# CLK_SYNTH.net
KiCad netlist of a schematic drawn in Altium Designer
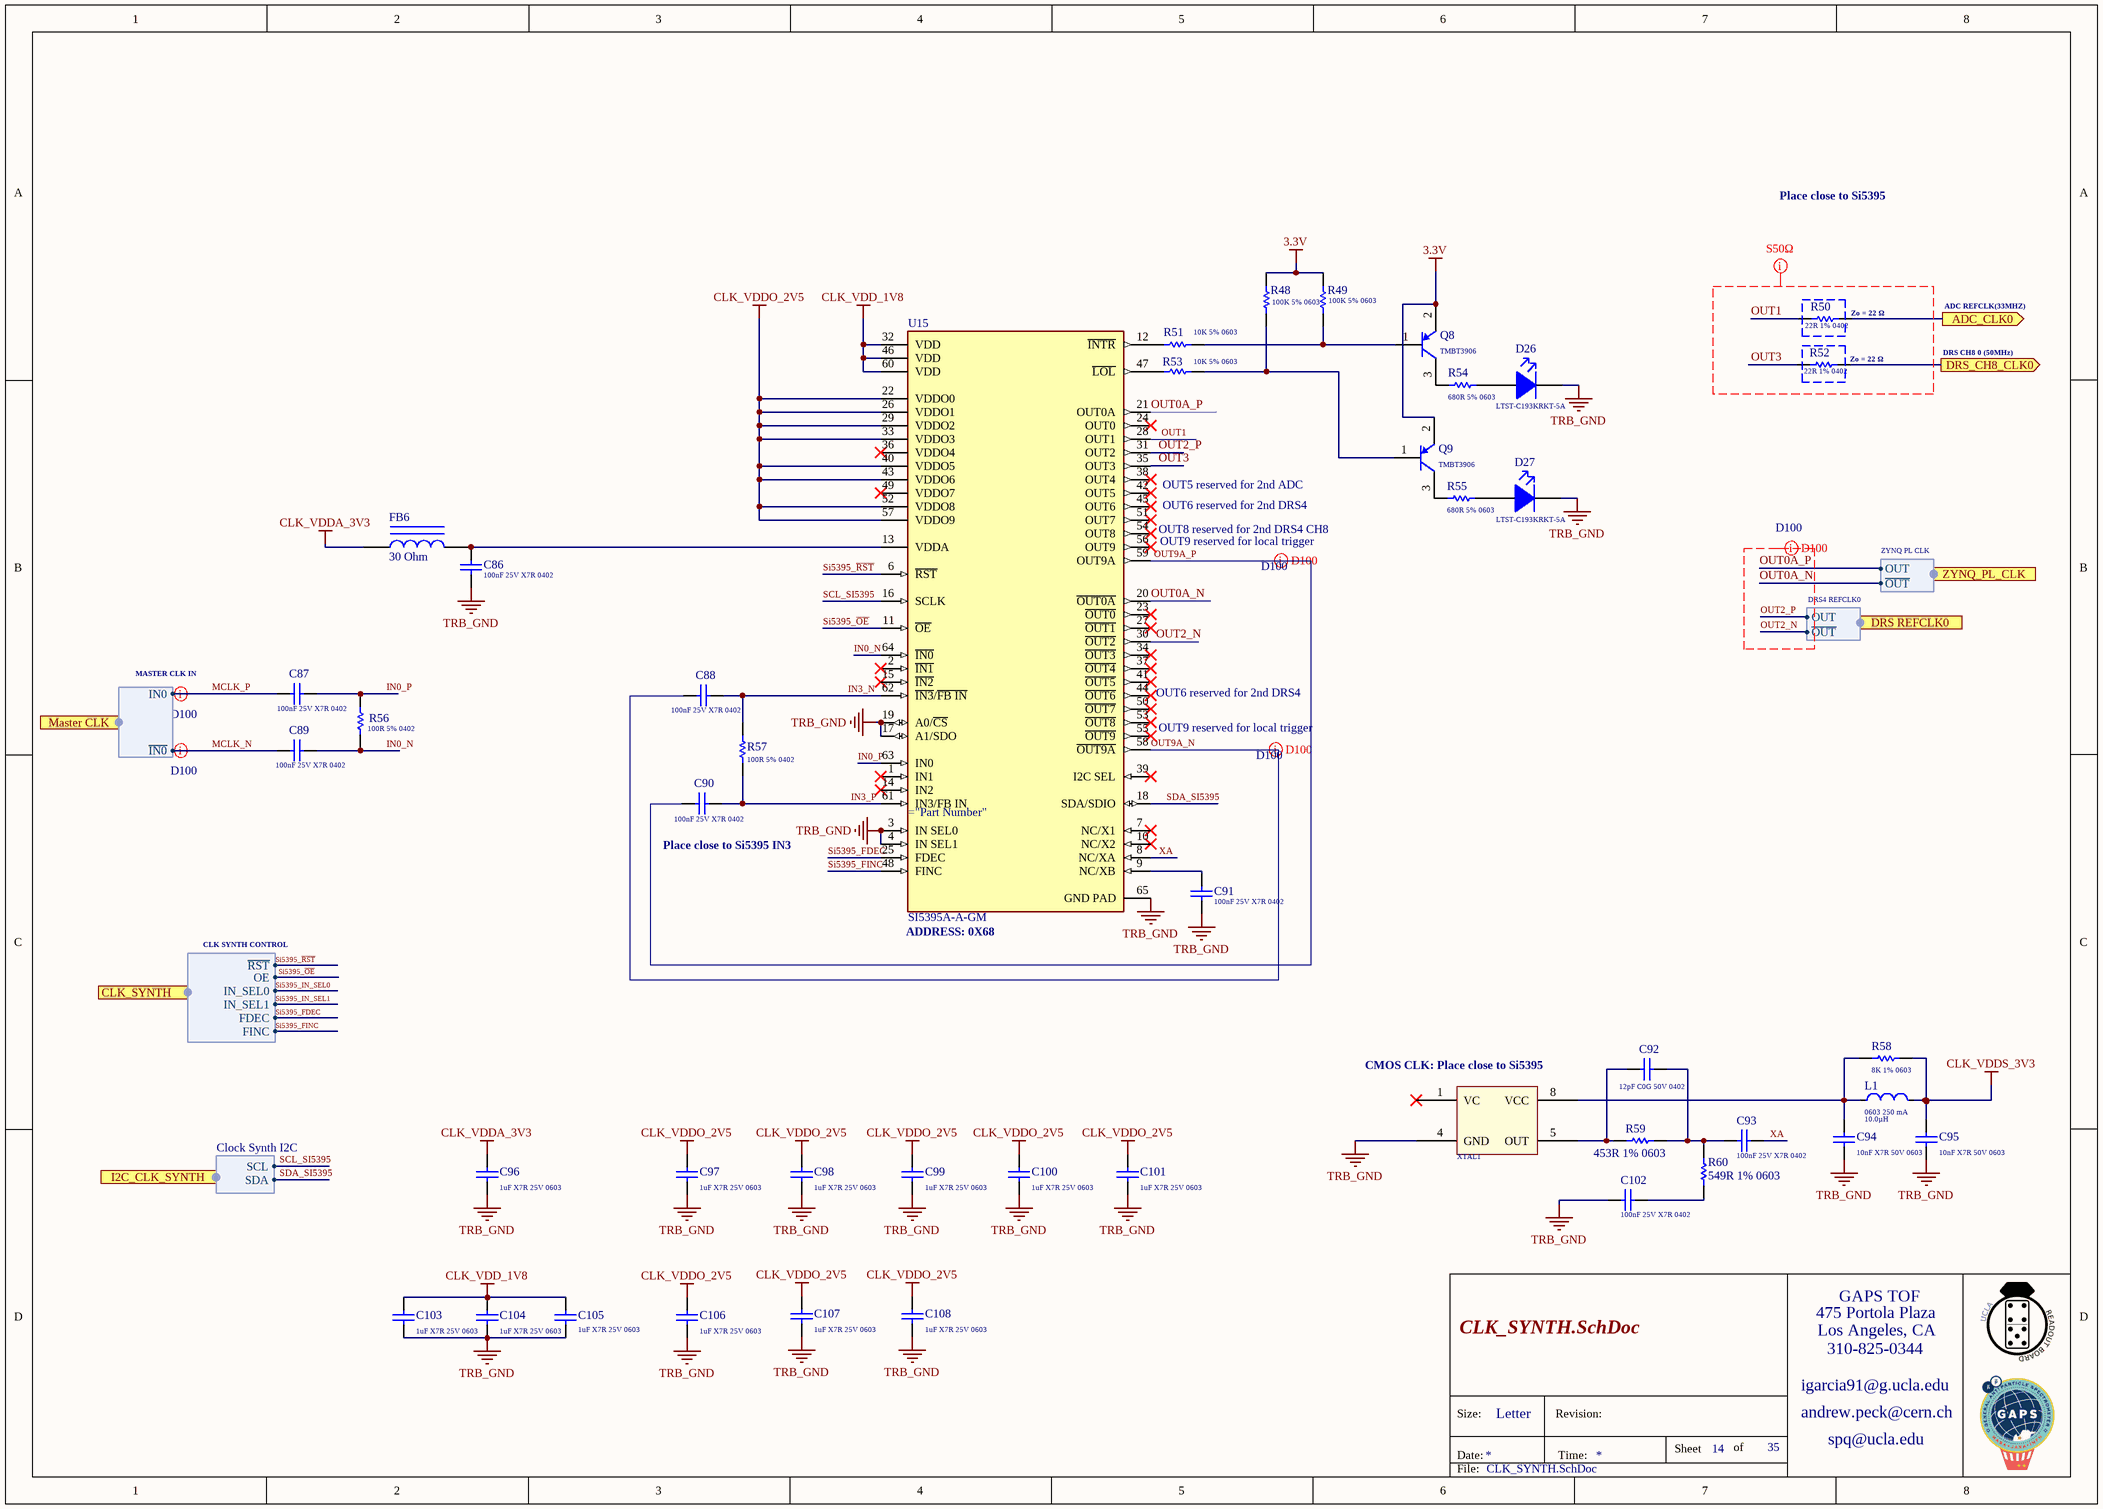
[diagram p0: CLK_SYNTH.SchDoc]

(export (version "E")
  (design (tool "Eeschema 10.0.6"))
  (components
    (comp (ref "C86")
      (value "Cap_Taiyo_Yuden_TMK105B7104KV-FR_100nF")
      (footprint "Cap_Taiyo_Yuden_TMK105B7104KV-FR_100nF")
      (description "CAP CER 100nF 25V X7R 0402")
      (fields (field (name "CAPACITANCE") "100nF 25V X7R 0402"))
      (libsource (lib "Cap_Taiyo_Yuden_TMK105B7104KV-FR_100nF") (part "Cap_Taiyo_Yuden_TMK105B7104KV-FR_100nF"))
    )
    (comp (ref "C87")
      (value "Cap_Taiyo_Yuden_TMK105B7104KV-FR_100nF")
      (footprint "Cap_Taiyo_Yuden_TMK105B7104KV-FR_100nF")
      (description "CAP CER 100nF 25V X7R 0402")
      (fields (field (name "CAPACITANCE") "100nF 25V X7R 0402"))
      (libsource (lib "Cap_Taiyo_Yuden_TMK105B7104KV-FR_100nF") (part "Cap_Taiyo_Yuden_TMK105B7104KV-FR_100nF"))
    )
    (comp (ref "C88")
      (value "Cap_Taiyo_Yuden_TMK105B7104KV-FR_100nF")
      (footprint "Cap_Taiyo_Yuden_TMK105B7104KV-FR_100nF")
      (description "CAP CER 100nF 25V X7R 0402")
      (fields (field (name "CAPACITANCE") "100nF 25V X7R 0402"))
      (libsource (lib "Cap_Taiyo_Yuden_TMK105B7104KV-FR_100nF") (part "Cap_Taiyo_Yuden_TMK105B7104KV-FR_100nF"))
    )
    (comp (ref "C89")
      (value "Cap_Taiyo_Yuden_TMK105B7104KV-FR_100nF")
      (footprint "Cap_Taiyo_Yuden_TMK105B7104KV-FR_100nF")
      (description "CAP CER 100nF 25V X7R 0402")
      (fields (field (name "CAPACITANCE") "100nF 25V X7R 0402"))
      (libsource (lib "Cap_Taiyo_Yuden_TMK105B7104KV-FR_100nF") (part "Cap_Taiyo_Yuden_TMK105B7104KV-FR_100nF"))
    )
    (comp (ref "C90")
      (value "Cap_Taiyo_Yuden_TMK105B7104KV-FR_100nF")
      (footprint "Cap_Taiyo_Yuden_TMK105B7104KV-FR_100nF")
      (description "CAP CER 100nF 25V X7R 0402")
      (fields (field (name "CAPACITANCE") "100nF 25V X7R 0402"))
      (libsource (lib "Cap_Taiyo_Yuden_TMK105B7104KV-FR_100nF") (part "Cap_Taiyo_Yuden_TMK105B7104KV-FR_100nF"))
    )
    (comp (ref "C91")
      (value "Cap_Taiyo_Yuden_TMK105B7104KV-FR_100nF")
      (footprint "Cap_Taiyo_Yuden_TMK105B7104KV-FR_100nF")
      (description "CAP CER 100nF 25V X7R 0402")
      (fields (field (name "CAPACITANCE") "100nF 25V X7R 0402"))
      (libsource (lib "Cap_Taiyo_Yuden_TMK105B7104KV-FR_100nF") (part "Cap_Taiyo_Yuden_TMK105B7104KV-FR_100nF"))
    )
    (comp (ref "C92")
      (value "Cap_Murata_GCQ1555C1H120FB01D_12pF")
      (footprint "Cap_Murata_GCQ1555C1H120FB01D_12pF")
      (description "MLCC - SMD/SMT 0402 50VDC 12pF 1% AEC-Q200")
      (fields (field (name "CAPACITANCE") "12pF C0G 50V 0402"))
      (libsource (lib "Cap_Murata_GCQ1555C1H120FB01D_12pF") (part "Cap_Murata_GCQ1555C1H120FB01D_12pF"))
    )
    (comp (ref "C93")
      (value "Cap_Taiyo_Yuden_TMK105B7104KV-FR_100nF")
      (footprint "Cap_Taiyo_Yuden_TMK105B7104KV-FR_100nF")
      (description "CAP CER 100nF 25V X7R 0402")
      (fields (field (name "CAPACITANCE") "100nF 25V X7R 0402"))
      (libsource (lib "Cap_Taiyo_Yuden_TMK105B7104KV-FR_100nF") (part "Cap_Taiyo_Yuden_TMK105B7104KV-FR_100nF"))
    )
    (comp (ref "C94")
      (value "Cap_Kemet_C0603C103J5RACTU_eec")
      (footprint "Kemet_C0603_0")
      (description "CAP CER 10nF 50V X7R 0603")
      (fields
        (field (name "PART NUMBER") "C0603C103J5RACTU")
        (field (name "MANUFACTURER") "Kemet")
        (field (name "CAPACITANCE") "10nF X7R 50V 0603")
      )
      (libsource (lib "Cap_Kemet_C0603C103J5RACTU_10nF") (part "Cap_Kemet_C0603C103J5RACTU_eec"))
    )
    (comp (ref "C95")
      (value "Cap_Kemet_C0603C103J5RACTU_eec")
      (footprint "Kemet_C0603_0")
      (description "CAP CER 10nF 50V X7R 0603")
      (fields
        (field (name "PART NUMBER") "C0603C103J5RACTU")
        (field (name "MANUFACTURER") "Kemet")
        (field (name "CAPACITANCE") "10nF X7R 50V 0603")
      )
      (libsource (lib "Cap_Kemet_C0603C103J5RACTU_10nF") (part "Cap_Kemet_C0603C103J5RACTU_eec"))
    )
    (comp (ref "C96")
      (value "Cap_Murata_GCJ188R71E105KA01J_1uF")
      (footprint "Cap_Murata_GCJ188R71E105KA01J_1uF")
      (description "CAP CER 1uF 25V X7R 0603")
      (fields (field (name "CAPACITANCE") "1uF X7R 25V 0603"))
      (libsource (lib "Cap_Murata_GCJ188R71E105KA01J_1uF") (part "Cap_Murata_GCJ188R71E105KA01J_1uF"))
    )
    (comp (ref "C97")
      (value "Cap_Murata_GCJ188R71E105KA01J_1uF")
      (footprint "Cap_Murata_GCJ188R71E105KA01J_1uF")
      (description "CAP CER 1uF 25V X7R 0603")
      (fields (field (name "CAPACITANCE") "1uF X7R 25V 0603"))
      (libsource (lib "Cap_Murata_GCJ188R71E105KA01J_1uF") (part "Cap_Murata_GCJ188R71E105KA01J_1uF"))
    )
    (comp (ref "C98")
      (value "Cap_Murata_GCJ188R71E105KA01J_1uF")
      (footprint "Cap_Murata_GCJ188R71E105KA01J_1uF")
      (description "CAP CER 1uF 25V X7R 0603")
      (fields (field (name "CAPACITANCE") "1uF X7R 25V 0603"))
      (libsource (lib "Cap_Murata_GCJ188R71E105KA01J_1uF") (part "Cap_Murata_GCJ188R71E105KA01J_1uF"))
    )
    (comp (ref "C99")
      (value "Cap_Murata_GCJ188R71E105KA01J_1uF")
      (footprint "Cap_Murata_GCJ188R71E105KA01J_1uF")
      (description "CAP CER 1uF 25V X7R 0603")
      (fields (field (name "CAPACITANCE") "1uF X7R 25V 0603"))
      (libsource (lib "Cap_Murata_GCJ188R71E105KA01J_1uF") (part "Cap_Murata_GCJ188R71E105KA01J_1uF"))
    )
    (comp (ref "C100")
      (value "Cap_Murata_GCJ188R71E105KA01J_1uF")
      (footprint "Cap_Murata_GCJ188R71E105KA01J_1uF")
      (description "CAP CER 1uF 25V X7R 0603")
      (fields (field (name "CAPACITANCE") "1uF X7R 25V 0603"))
      (libsource (lib "Cap_Murata_GCJ188R71E105KA01J_1uF") (part "Cap_Murata_GCJ188R71E105KA01J_1uF"))
    )
    (comp (ref "C101")
      (value "Cap_Murata_GCJ188R71E105KA01J_1uF")
      (footprint "Cap_Murata_GCJ188R71E105KA01J_1uF")
      (description "CAP CER 1uF 25V X7R 0603")
      (fields (field (name "CAPACITANCE") "1uF X7R 25V 0603"))
      (libsource (lib "Cap_Murata_GCJ188R71E105KA01J_1uF") (part "Cap_Murata_GCJ188R71E105KA01J_1uF"))
    )
    (comp (ref "C102")
      (value "Cap_Taiyo_Yuden_TMK105B7104KV-FR_100nF")
      (footprint "Cap_Taiyo_Yuden_TMK105B7104KV-FR_100nF")
      (description "CAP CER 100nF 25V X7R 0402")
      (fields (field (name "CAPACITANCE") "100nF 25V X7R 0402"))
      (libsource (lib "Cap_Taiyo_Yuden_TMK105B7104KV-FR_100nF") (part "Cap_Taiyo_Yuden_TMK105B7104KV-FR_100nF"))
    )
    (comp (ref "C103")
      (value "Cap_Murata_GCJ188R71E105KA01J_1uF")
      (footprint "Cap_Murata_GCJ188R71E105KA01J_1uF")
      (description "CAP CER 1uF 25V X7R 0603")
      (fields (field (name "CAPACITANCE") "1uF X7R 25V 0603"))
      (libsource (lib "Cap_Murata_GCJ188R71E105KA01J_1uF") (part "Cap_Murata_GCJ188R71E105KA01J_1uF"))
    )
    (comp (ref "C104")
      (value "Cap_Murata_GCJ188R71E105KA01J_1uF")
      (footprint "Cap_Murata_GCJ188R71E105KA01J_1uF")
      (description "CAP CER 1uF 25V X7R 0603")
      (fields (field (name "CAPACITANCE") "1uF X7R 25V 0603"))
      (libsource (lib "Cap_Murata_GCJ188R71E105KA01J_1uF") (part "Cap_Murata_GCJ188R71E105KA01J_1uF"))
    )
    (comp (ref "C105")
      (value "Cap_Murata_GCJ188R71E105KA01J_1uF")
      (footprint "Cap_Murata_GCJ188R71E105KA01J_1uF")
      (description "CAP CER 1uF 25V X7R 0603")
      (fields (field (name "CAPACITANCE") "1uF X7R 25V 0603"))
      (libsource (lib "Cap_Murata_GCJ188R71E105KA01J_1uF") (part "Cap_Murata_GCJ188R71E105KA01J_1uF"))
    )
    (comp (ref "C106")
      (value "Cap_Murata_GCJ188R71E105KA01J_1uF")
      (footprint "Cap_Murata_GCJ188R71E105KA01J_1uF")
      (description "CAP CER 1uF 25V X7R 0603")
      (fields (field (name "CAPACITANCE") "1uF X7R 25V 0603"))
      (libsource (lib "Cap_Murata_GCJ188R71E105KA01J_1uF") (part "Cap_Murata_GCJ188R71E105KA01J_1uF"))
    )
    (comp (ref "C107")
      (value "Cap_Murata_GCJ188R71E105KA01J_1uF")
      (footprint "Cap_Murata_GCJ188R71E105KA01J_1uF")
      (description "CAP CER 1uF 25V X7R 0603")
      (fields (field (name "CAPACITANCE") "1uF X7R 25V 0603"))
      (libsource (lib "Cap_Murata_GCJ188R71E105KA01J_1uF") (part "Cap_Murata_GCJ188R71E105KA01J_1uF"))
    )
    (comp (ref "C108")
      (value "Cap_Murata_GCJ188R71E105KA01J_1uF")
      (footprint "Cap_Murata_GCJ188R71E105KA01J_1uF")
      (description "CAP CER 1uF 25V X7R 0603")
      (fields (field (name "CAPACITANCE") "1uF X7R 25V 0603"))
      (libsource (lib "Cap_Murata_GCJ188R71E105KA01J_1uF") (part "Cap_Murata_GCJ188R71E105KA01J_1uF"))
    )
    (comp (ref "D26")
      (value "LTST-C193KRKT-5A")
      (footprint "Led_Lite-On_LTST-C193KGKT-5A_Red")
      (description "Standard LEDs - SMD Red 470nm 28mcd 20mA")
      (fields (field (name "SERIES") "LTST-C193KRKT-5A"))
      (libsource (lib "Led_Lite-On_LTST-C193KGKT-5A_Red") (part "Led_Lite-On_LTST-C193KGKT-5A_Red"))
    )
    (comp (ref "D27")
      (value "LTST-C193KRKT-5A")
      (footprint "Led_Lite-On_LTST-C193KGKT-5A_Red")
      (description "Standard LEDs - SMD Red 470nm 28mcd 20mA")
      (fields (field (name "SERIES") "LTST-C193KRKT-5A"))
      (libsource (lib "Led_Lite-On_LTST-C193KGKT-5A_Red") (part "Led_Lite-On_LTST-C193KGKT-5A_Red"))
    )
    (comp (ref "FB6")
      (value "30 Ohm")
      (footprint "Feb_MURATA_BLM15AX300SZ1D_30")
      (description "Feb SMD 30 OHM 25% 3/4W 0402")
      (libsource (lib "Feb_MURATA_BLM15AX300SZ1D_30") (part "Feb_MURATA_BLM15AX300SZ1D_30"))
    )
    (comp (ref "L1")
      (value "0603 250 mA")
      (footprint "TDK_MLZ1608M100WT_0")
      (description "IND 10µH Shielded Multilayer Inductor 250mA 1.365 Ohm Max 0603 (1608 Metric)")
      (fields
        (field (name "PART NUMBER") "MLZ1608M100WT")
        (field (name "MANUFACTURER") "TDK")
        (field (name "INDUCTANCE") "10.0µH")
      )
      (libsource (lib "Ind_TDK_MLZ1608M100WT_10uH") (part "Ind_TDK_MLZ1608M100WT_eec"))
    )
    (comp (ref "Q8")
      (value "BJT_PNP_Toshiba_TMBT3906")
      (footprint "BJT_PNP_Toshiba_TMBT3906")
      (description "Bipolar Transistors - BJT Transistor for Low Freq. Amplification")
      (fields (field (name "SERIES") "TMBT3906") (field (name "MANUFACTURER") "Toshiba"))
      (libsource (lib "BJT_PNP_Toshiba_TMBT3906") (part "BJT_PNP_Toshiba_TMBT3906"))
    )
    (comp (ref "Q9")
      (value "BJT_PNP_Toshiba_TMBT3906")
      (footprint "BJT_PNP_Toshiba_TMBT3906")
      (description "Bipolar Transistors - BJT Transistor for Low Freq. Amplification")
      (fields (field (name "SERIES") "TMBT3906") (field (name "MANUFACTURER") "Toshiba"))
      (libsource (lib "BJT_PNP_Toshiba_TMBT3906") (part "BJT_PNP_Toshiba_TMBT3906"))
    )
    (comp (ref "R48")
      (value "100K 5% 0603")
      (footprint "RESC0603(1608)_N")
      (description "100K 0.1W 5% 0603 (1608 Metric)  SMD")
      (fields (field (name "TOLERANCE") "5 %") (field (name "POWER") "0.1 W"))
      (libsource (lib "Altium Content Vault") (part "RES"))
    )
    (comp (ref "R49")
      (value "100K 5% 0603")
      (footprint "RESC0603(1608)_N")
      (description "100K 0.1W 5% 0603 (1608 Metric)  SMD")
      (fields (field (name "TOLERANCE") "5 %") (field (name "POWER") "0.1 W"))
      (libsource (lib "Altium Content Vault") (part "RES"))
    )
    (comp (ref "R50")
      (value "22R 1% 0402")
      (footprint "RESC0402(1005)_L")
      (description "22R 0.063W 1% 0402 (1005 Metric)  SMD")
      (fields (field (name "TOLERANCE") "1 %") (field (name "POWER") "0.063 W"))
      (libsource (lib "Altium Content Vault") (part "RES"))
    )
    (comp (ref "R51")
      (value "10K 5% 0603")
      (footprint "RESC0603(1608)_L")
      (description "10K 0.1W 5% 0603 (1608 Metric)  SMD")
      (fields (field (name "TOLERANCE") "5 %") (field (name "POWER") "0.1 W"))
      (libsource (lib "Altium Content Vault") (part "RES"))
    )
    (comp (ref "R52")
      (value "22R 1% 0402")
      (footprint "RESC0402(1005)_L")
      (description "22R 0.063W 1% 0402 (1005 Metric)  SMD")
      (fields (field (name "TOLERANCE") "1 %") (field (name "POWER") "0.063 W"))
      (libsource (lib "Altium Content Vault") (part "RES"))
    )
    (comp (ref "R53")
      (value "10K 5% 0603")
      (footprint "RESC0603(1608)_L")
      (description "10K 0.1W 5% 0603 (1608 Metric)  SMD")
      (fields (field (name "TOLERANCE") "5 %") (field (name "POWER") "0.1 W"))
      (libsource (lib "Altium Content Vault") (part "RES"))
    )
    (comp (ref "R54")
      (value "680R 5% 0603")
      (footprint "RESC0603(1608)_L")
      (description "680R 0.1W 5% 0603 (1608 Metric)  SMD")
      (fields (field (name "TOLERANCE") "5 %") (field (name "POWER") "0.1 W"))
      (libsource (lib "Altium Content Vault") (part "RES"))
    )
    (comp (ref "R55")
      (value "680R 5% 0603")
      (footprint "RESC0603(1608)_L")
      (description "680R 0.1W 5% 0603 (1608 Metric)  SMD")
      (fields (field (name "TOLERANCE") "5 %") (field (name "POWER") "0.1 W"))
      (libsource (lib "Altium Content Vault") (part "RES"))
    )
    (comp (ref "R56")
      (value "100R 5% 0402")
      (footprint "RESC0402(1005)_L")
      (description "100R 0.063W 5% 0402 (1005 Metric)  SMD")
      (fields (field (name "TOLERANCE") "5 %") (field (name "POWER") "0.063 W"))
      (libsource (lib "Altium Content Vault") (part "RES"))
    )
    (comp (ref "R57")
      (value "100R 5% 0402")
      (footprint "RESC0402(1005)_L")
      (description "100R 0.063W 5% 0402 (1005 Metric)  SMD")
      (fields (field (name "TOLERANCE") "5 %") (field (name "POWER") "0.063 W"))
      (libsource (lib "Altium Content Vault") (part "RES"))
    )
    (comp (ref "R58")
      (value "8K 1% 0603")
      (footprint "Res_Yageo_RT0603BRE078KL_8K")
      (description "8K 0.1W 1% 0603 (1608 Metric)  SMD")
      (libsource (lib "Res_Yageo_RT0603BRE078KL_8K") (part "Res_Yageo_RT0603BRE078KL_8K"))
    )
    (comp (ref "R59")
      (value "453R 1% 0603")
      (footprint "RESC1608X55X30NL15T15")
      (description "ERJ-3EKF4530V")
      (fields (field (name "MANUFACTURER") "Panasonic"))
      (libsource (lib "Altium Content Vault") (part "RES"))
    )
    (comp (ref "R60")
      (value "549R 1% 0603")
      (footprint "RESC1608X55X30NL15T15")
      (description "ERJ-3EKF5490V")
      (fields (field (name "MANUFACTURER") "Panasonic"))
      (libsource (lib "Altium Content Vault") (part "RES"))
    )
    (comp (ref "U15")
      (value "IC_Silicon_Laboratories_ SI5395A-A-GM_CLK")
      (footprint "Si5395")
      (fields (field (name "SERIES") "SI5395A-A-GM"))
      (libsource (lib "SI5395A-A-GM") (part "IC_Silicon_Laboratories_ SI5395A-A-GM_CLK"))
    )
    (comp (ref "XTAL1")
      (value "TCXO_Murata_XTCLH50M000CHJA3P0_50MHz")
      (footprint "TCXO_Murata_XTCLH50M000CHJA3P0_50MHz")
      (description "TCXO Oscillators 50MHz 5x3.2x1.5mm 0.2ppm max Crystal")
      (libsource (lib "TCXO_Murata_XTCLH50M000CHJA3P0_50MHz") (part "TCXO_Murata_XTCLH50M000CHJA3P0_50MHz"))
    )
  )
  (nets
    (net (code "13") (name "/ADC_CLK0") (class "Default")
      (node (ref "R50") (pin "1") (pinfunction "1_1") (pintype "passive"))
    )
    (net (code "14") (name "/DRS_CH8_CLK0") (class "Default")
      (node (ref "R52") (pin "1") (pinfunction "1_1") (pintype "passive"))
    )
    (net (code "15") (name "/IN0_N") (class "Default")
      (node (ref "C89") (pin "2") (pinfunction "2_2") (pintype "passive"))
      (node (ref "R56") (pin "1") (pinfunction "1_1") (pintype "passive"))
      (node (ref "U15") (pin "64") (pinfunction "~{IN0}_64") (pintype "input"))
    )
    (net (code "16") (name "/IN0_P") (class "Default")
      (node (ref "C87") (pin "2") (pinfunction "2_2") (pintype "passive"))
      (node (ref "R56") (pin "2") (pinfunction "2_2") (pintype "passive"))
      (node (ref "U15") (pin "63") (pinfunction "IN0_63") (pintype "input"))
    )
    (net (code "17") (name "/IN3_N") (class "Default")
      (node (ref "C88") (pin "2") (pinfunction "2_2") (pintype "passive"))
      (node (ref "R57") (pin "2") (pinfunction "2_2") (pintype "passive"))
      (node (ref "U15") (pin "62") (pinfunction "~{IN3}/~{FB_IN}_62") (pintype "input"))
    )
    (net (code "18") (name "/IN3_P") (class "Default")
      (node (ref "C90") (pin "2") (pinfunction "2_2") (pintype "passive"))
      (node (ref "R57") (pin "1") (pinfunction "1_1") (pintype "passive"))
      (node (ref "U15") (pin "61") (pinfunction "IN3/FB_IN_61") (pintype "input"))
    )
    (net (code "19") (name "/MCLK_N") (class "Default")
      (node (ref "C89") (pin "1") (pinfunction "1_1") (pintype "passive"))
    )
    (net (code "20") (name "/MCLK_P") (class "Default")
      (node (ref "C87") (pin "1") (pinfunction "1_1") (pintype "passive"))
    )
    (net (code "21") (name "/OUT0A_N") (class "Default")
      (node (ref "U15") (pin "20") (pinfunction "~{OUT0A}_20") (pintype "output"))
    )
    (net (code "22") (name "/OUT0A_P") (class "Default")
      (node (ref "U15") (pin "21") (pinfunction "OUT0A_21") (pintype "output"))
    )
    (net (code "23") (name "/OUT1") (class "Default")
      (node (ref "R50") (pin "2") (pinfunction "2_2") (pintype "passive"))
      (node (ref "U15") (pin "28") (pinfunction "OUT1_28") (pintype "output"))
    )
    (net (code "24") (name "/OUT2_N") (class "Default")
      (node (ref "U15") (pin "30") (pinfunction "~{OUT2}_30") (pintype "output"))
    )
    (net (code "25") (name "/OUT2_P") (class "Default")
      (node (ref "U15") (pin "31") (pinfunction "OUT2_31") (pintype "output"))
    )
    (net (code "26") (name "/OUT3") (class "Default")
      (node (ref "R52") (pin "2") (pinfunction "2_2") (pintype "passive"))
      (node (ref "U15") (pin "35") (pinfunction "OUT3_35") (pintype "output"))
    )
    (net (code "27") (name "/OUT9A_N") (class "Default")
      (node (ref "C88") (pin "1") (pinfunction "1_1") (pintype "passive"))
      (node (ref "U15") (pin "58") (pinfunction "~{OUT9A}_58") (pintype "output"))
    )
    (net (code "28") (name "/OUT9A_P") (class "Default")
      (node (ref "C90") (pin "1") (pinfunction "1_1") (pintype "passive"))
      (node (ref "U15") (pin "59") (pinfunction "OUT9A_59") (pintype "output"))
    )
    (net (code "29") (name "/SCL_SI5395") (class "Default")
      (node (ref "U15") (pin "16") (pinfunction "SCLK_16") (pintype "input"))
    )
    (net (code "30") (name "/SDA_SI5395") (class "Default")
      (node (ref "U15") (pin "18") (pinfunction "SDA/SDIO_18") (pintype "bidirectional"))
    )
    (net (code "31") (name "/Si5395_FDEC") (class "Default")
      (node (ref "U15") (pin "25") (pinfunction "FDEC_25") (pintype "input"))
    )
    (net (code "32") (name "/Si5395_FINC") (class "Default")
      (node (ref "U15") (pin "48") (pinfunction "FINC_48") (pintype "input"))
    )
    (net (code "35") (name "/Si5395_~{OE}") (class "Default")
      (node (ref "U15") (pin "11") (pinfunction "~{OE}_11") (pintype "input"))
    )
    (net (code "36") (name "/Si5395_~{RST}") (class "Default")
      (node (ref "U15") (pin "6") (pinfunction "~{RST}_6") (pintype "input"))
    )
    (net (code "37") (name "/XA") (class "Default")
      (node (ref "C93") (pin "2") (pinfunction "2_2") (pintype "passive"))
      (node (ref "U15") (pin "8") (pinfunction "NC/XA_8") (pintype "input"))
    )
    (net (code "43") (name "3.3V") (class "Default")
      (node (ref "Q8") (pin "2") (pinfunction "E_2") (pintype "passive"))
      (node (ref "Q9") (pin "2") (pinfunction "E_2") (pintype "passive"))
      (node (ref "R48") (pin "2") (pinfunction "2_2") (pintype "passive"))
      (node (ref "R49") (pin "2") (pinfunction "2_2") (pintype "passive"))
    )
    (net (code "44") (name "CLK_VDDA_3V3") (class "Default")
      (node (ref "C96") (pin "2") (pinfunction "2_2") (pintype "passive"))
      (node (ref "FB6") (pin "1") (pinfunction "1_1") (pintype "passive"))
    )
    (net (code "45") (name "CLK_VDDO_2V5") (class "Default")
      (node (ref "C100") (pin "2") (pinfunction "2_2") (pintype "passive"))
      (node (ref "C101") (pin "2") (pinfunction "2_2") (pintype "passive"))
      (node (ref "C106") (pin "2") (pinfunction "2_2") (pintype "passive"))
      (node (ref "C107") (pin "2") (pinfunction "2_2") (pintype "passive"))
      (node (ref "C108") (pin "2") (pinfunction "2_2") (pintype "passive"))
      (node (ref "C97") (pin "2") (pinfunction "2_2") (pintype "passive"))
      (node (ref "C98") (pin "2") (pinfunction "2_2") (pintype "passive"))
      (node (ref "C99") (pin "2") (pinfunction "2_2") (pintype "passive"))
      (node (ref "U15") (pin "22") (pinfunction "VDDO0_22") (pintype "power_in"))
      (node (ref "U15") (pin "26") (pinfunction "VDDO1_26") (pintype "power_in"))
      (node (ref "U15") (pin "29") (pinfunction "VDDO2_29") (pintype "power_in"))
      (node (ref "U15") (pin "33") (pinfunction "VDDO3_33") (pintype "power_in"))
      (node (ref "U15") (pin "40") (pinfunction "VDDO5_40") (pintype "power_in"))
      (node (ref "U15") (pin "43") (pinfunction "VDDO6_43") (pintype "power_in"))
      (node (ref "U15") (pin "52") (pinfunction "VDDO8_52") (pintype "power_in"))
      (node (ref "U15") (pin "57") (pinfunction "VDDO9_57") (pintype "power_in"))
    )
    (net (code "46") (name "CLK_VDDS_3V3") (class "Default")
      (node (ref "C95") (pin "1") (pinfunction "1_1") (pintype "passive"))
      (node (ref "L1") (pin "2") (pinfunction "2_2") (pintype "passive"))
      (node (ref "R58") (pin "2") (pinfunction "2_2") (pintype "passive"))
    )
    (net (code "47") (name "CLK_VDD_1V8") (class "Default")
      (node (ref "C103") (pin "2") (pinfunction "2_2") (pintype "passive"))
      (node (ref "C104") (pin "2") (pinfunction "2_2") (pintype "passive"))
      (node (ref "C105") (pin "2") (pinfunction "2_2") (pintype "passive"))
      (node (ref "U15") (pin "32") (pinfunction "VDD_32") (pintype "power_in"))
      (node (ref "U15") (pin "46") (pinfunction "VDD_46") (pintype "power_in"))
      (node (ref "U15") (pin "60") (pinfunction "VDD_60") (pintype "power_in"))
    )
    (net (code "48") (name "Net-(C92-Pad1)") (class "Default")
      (node (ref "C92") (pin "1") (pinfunction "1_1") (pintype "passive"))
      (node (ref "C93") (pin "1") (pinfunction "1_1") (pintype "passive"))
      (node (ref "R59") (pin "2") (pinfunction "2_2") (pintype "passive"))
      (node (ref "R60") (pin "2") (pinfunction "2_2") (pintype "passive"))
    )
    (net (code "49") (name "Net-(C102-Pad2)") (class "Default")
      (node (ref "C102") (pin "2") (pinfunction "2_2") (pintype "passive"))
      (node (ref "R60") (pin "1") (pinfunction "1_1") (pintype "passive"))
    )
    (net (code "50") (name "Net-(D26-A)") (class "Default")
      (node (ref "D26") (pin "2") (pinfunction "A_2") (pintype "passive"))
      (node (ref "R54") (pin "2") (pinfunction "2_2") (pintype "passive"))
    )
    (net (code "51") (name "Net-(D27-A)") (class "Default")
      (node (ref "D27") (pin "2") (pinfunction "A_2") (pintype "passive"))
      (node (ref "R55") (pin "2") (pinfunction "2_2") (pintype "passive"))
    )
    (net (code "52") (name "Net-(Q8-B)") (class "Default")
      (node (ref "Q8") (pin "1") (pinfunction "B_1") (pintype "passive"))
      (node (ref "R49") (pin "1") (pinfunction "1_1") (pintype "passive"))
      (node (ref "R51") (pin "1") (pinfunction "1_1") (pintype "passive"))
    )
    (net (code "53") (name "Net-(Q8-C)") (class "Default")
      (node (ref "Q8") (pin "3") (pinfunction "C_3") (pintype "passive"))
      (node (ref "R54") (pin "1") (pinfunction "1_1") (pintype "passive"))
    )
    (net (code "54") (name "Net-(Q9-B)") (class "Default")
      (node (ref "Q9") (pin "1") (pinfunction "B_1") (pintype "passive"))
      (node (ref "R48") (pin "1") (pinfunction "1_1") (pintype "passive"))
      (node (ref "R53") (pin "1") (pinfunction "1_1") (pintype "passive"))
    )
    (net (code "55") (name "Net-(Q9-C)") (class "Default")
      (node (ref "Q9") (pin "3") (pinfunction "C_3") (pintype "passive"))
      (node (ref "R55") (pin "1") (pinfunction "1_1") (pintype "passive"))
    )
    (net (code "56") (name "Net-(U15-NC{slash}XB)") (class "Default")
      (node (ref "C91") (pin "2") (pinfunction "2_2") (pintype "passive"))
      (node (ref "U15") (pin "9") (pinfunction "NC/XB_9") (pintype "input"))
    )
    (net (code "57") (name "Net-(U15-VDDA)") (class "Default")
      (node (ref "C86") (pin "2") (pinfunction "2_2") (pintype "passive"))
      (node (ref "FB6") (pin "2") (pinfunction "2_2") (pintype "passive"))
      (node (ref "U15") (pin "13") (pinfunction "VDDA_13") (pintype "power_in"))
    )
    (net (code "58") (name "Net-(U15-~{INTR})") (class "Default")
      (node (ref "R51") (pin "2") (pinfunction "2_2") (pintype "passive"))
      (node (ref "U15") (pin "12") (pinfunction "~{INTR}_12") (pintype "output"))
    )
    (net (code "59") (name "Net-(U15-~{LOL})") (class "Default")
      (node (ref "R53") (pin "2") (pinfunction "2_2") (pintype "passive"))
      (node (ref "U15") (pin "47") (pinfunction "~{LOL}_47") (pintype "output"))
    )
    (net (code "60") (name "Net-(XTAL1-OUT)") (class "Default")
      (node (ref "C92") (pin "2") (pinfunction "2_2") (pintype "passive"))
      (node (ref "R59") (pin "1") (pinfunction "1_1") (pintype "passive"))
      (node (ref "XTAL1") (pin "5") (pinfunction "OUT_5") (pintype "passive"))
    )
    (net (code "61") (name "Net-(XTAL1-VCC)") (class "Default")
      (node (ref "C94") (pin "1") (pinfunction "1_1") (pintype "passive"))
      (node (ref "L1") (pin "1") (pinfunction "1_1") (pintype "passive"))
      (node (ref "R58") (pin "1") (pinfunction "1_1") (pintype "passive"))
      (node (ref "XTAL1") (pin "8") (pinfunction "VCC_8") (pintype "passive"))
    )
    (net (code "62") (name "TRB_GND") (class "Default")
      (node (ref "C100") (pin "1") (pinfunction "1_1") (pintype "passive"))
      (node (ref "C101") (pin "1") (pinfunction "1_1") (pintype "passive"))
      (node (ref "C102") (pin "1") (pinfunction "1_1") (pintype "passive"))
      (node (ref "C103") (pin "1") (pinfunction "1_1") (pintype "passive"))
      (node (ref "C104") (pin "1") (pinfunction "1_1") (pintype "passive"))
      (node (ref "C105") (pin "1") (pinfunction "1_1") (pintype "passive"))
      (node (ref "C106") (pin "1") (pinfunction "1_1") (pintype "passive"))
      (node (ref "C107") (pin "1") (pinfunction "1_1") (pintype "passive"))
      (node (ref "C108") (pin "1") (pinfunction "1_1") (pintype "passive"))
      (node (ref "C86") (pin "1") (pinfunction "1_1") (pintype "passive"))
      (node (ref "C91") (pin "1") (pinfunction "1_1") (pintype "passive"))
      (node (ref "C94") (pin "2") (pinfunction "2_2") (pintype "passive"))
      (node (ref "C95") (pin "2") (pinfunction "2_2") (pintype "passive"))
      (node (ref "C96") (pin "1") (pinfunction "1_1") (pintype "passive"))
      (node (ref "C97") (pin "1") (pinfunction "1_1") (pintype "passive"))
      (node (ref "C98") (pin "1") (pinfunction "1_1") (pintype "passive"))
      (node (ref "C99") (pin "1") (pinfunction "1_1") (pintype "passive"))
      (node (ref "D26") (pin "1") (pinfunction "K_1") (pintype "passive"))
      (node (ref "D27") (pin "1") (pinfunction "K_1") (pintype "passive"))
      (node (ref "U15") (pin "17") (pinfunction "A1/SDO_17") (pintype "bidirectional"))
      (node (ref "U15") (pin "19") (pinfunction "A0/~{CS}_19") (pintype "bidirectional"))
      (node (ref "U15") (pin "3") (pinfunction "IN_SEL0_3") (pintype "input"))
      (node (ref "U15") (pin "4") (pinfunction "IN_SEL1_4") (pintype "input"))
      (node (ref "U15") (pin "65") (pinfunction "GND_PAD_65") (pintype "power_in"))
      (node (ref "XTAL1") (pin "4") (pinfunction "GND_4") (pintype "passive"))
    )
    (net (code "63") (name "unconnected-(U15-I2C_SEL-Pad39)") (class "Default")
      (node (ref "U15") (pin "39") (pinfunction "I2C_SEL_39") (pintype "input+no_connect"))
    )
    (net (code "64") (name "unconnected-(U15-IN1-Pad1)") (class "Default")
      (node (ref "U15") (pin "1") (pinfunction "IN1_1") (pintype "input+no_connect"))
    )
    (net (code "65") (name "unconnected-(U15-IN2-Pad14)") (class "Default")
      (node (ref "U15") (pin "14") (pinfunction "IN2_14") (pintype "input+no_connect"))
    )
    (net (code "66") (name "unconnected-(U15-NC{slash}X1-Pad7)") (class "Default")
      (node (ref "U15") (pin "7") (pinfunction "NC/X1_7") (pintype "input+no_connect"))
    )
    (net (code "67") (name "unconnected-(U15-NC{slash}X2-Pad10)") (class "Default")
      (node (ref "U15") (pin "10") (pinfunction "NC/X2_10") (pintype "input+no_connect"))
    )
    (net (code "68") (name "unconnected-(U15-OUT0-Pad24)") (class "Default")
      (node (ref "U15") (pin "24") (pinfunction "OUT0_24") (pintype "output+no_connect"))
    )
    (net (code "69") (name "unconnected-(U15-OUT4-Pad38)") (class "Default")
      (node (ref "U15") (pin "38") (pinfunction "OUT4_38") (pintype "output+no_connect"))
    )
    (net (code "70") (name "unconnected-(U15-OUT5-Pad42)") (class "Default")
      (node (ref "U15") (pin "42") (pinfunction "OUT5_42") (pintype "output+no_connect"))
    )
    (net (code "71") (name "unconnected-(U15-OUT6-Pad45)") (class "Default")
      (node (ref "U15") (pin "45") (pinfunction "OUT6_45") (pintype "output+no_connect"))
    )
    (net (code "72") (name "unconnected-(U15-OUT7-Pad51)") (class "Default")
      (node (ref "U15") (pin "51") (pinfunction "OUT7_51") (pintype "output+no_connect"))
    )
    (net (code "73") (name "unconnected-(U15-OUT8-Pad54)") (class "Default")
      (node (ref "U15") (pin "54") (pinfunction "OUT8_54") (pintype "output+no_connect"))
    )
    (net (code "74") (name "unconnected-(U15-OUT9-Pad56)") (class "Default")
      (node (ref "U15") (pin "56") (pinfunction "OUT9_56") (pintype "output+no_connect"))
    )
    (net (code "75") (name "unconnected-(U15-VDDO4-Pad36)") (class "Default")
      (node (ref "U15") (pin "36") (pinfunction "VDDO4_36") (pintype "power_in+no_connect"))
    )
    (net (code "76") (name "unconnected-(U15-VDDO7-Pad49)") (class "Default")
      (node (ref "U15") (pin "49") (pinfunction "VDDO7_49") (pintype "power_in+no_connect"))
    )
    (net (code "77") (name "unconnected-(U15-~{IN1}-Pad2)") (class "Default")
      (node (ref "U15") (pin "2") (pinfunction "~{IN1}_2") (pintype "input+no_connect"))
    )
    (net (code "78") (name "unconnected-(U15-~{IN2}-Pad15)") (class "Default")
      (node (ref "U15") (pin "15") (pinfunction "~{IN2}_15") (pintype "input+no_connect"))
    )
    (net (code "79") (name "unconnected-(U15-~{OUT0}-Pad23)") (class "Default")
      (node (ref "U15") (pin "23") (pinfunction "~{OUT0}_23") (pintype "output+no_connect"))
    )
    (net (code "80") (name "unconnected-(U15-~{OUT1}-Pad27)") (class "Default")
      (node (ref "U15") (pin "27") (pinfunction "~{OUT1}_27") (pintype "output+no_connect"))
    )
    (net (code "81") (name "unconnected-(U15-~{OUT3}-Pad34)") (class "Default")
      (node (ref "U15") (pin "34") (pinfunction "~{OUT3}_34") (pintype "output+no_connect"))
    )
    (net (code "82") (name "unconnected-(U15-~{OUT4}-Pad37)") (class "Default")
      (node (ref "U15") (pin "37") (pinfunction "~{OUT4}_37") (pintype "output+no_connect"))
    )
    (net (code "83") (name "unconnected-(U15-~{OUT5}-Pad41)") (class "Default")
      (node (ref "U15") (pin "41") (pinfunction "~{OUT5}_41") (pintype "output+no_connect"))
    )
    (net (code "84") (name "unconnected-(U15-~{OUT6}-Pad44)") (class "Default")
      (node (ref "U15") (pin "44") (pinfunction "~{OUT6}_44") (pintype "output+no_connect"))
    )
    (net (code "85") (name "unconnected-(U15-~{OUT7}-Pad50)") (class "Default")
      (node (ref "U15") (pin "50") (pinfunction "~{OUT7}_50") (pintype "output+no_connect"))
    )
    (net (code "86") (name "unconnected-(U15-~{OUT8}-Pad53)") (class "Default")
      (node (ref "U15") (pin "53") (pinfunction "~{OUT8}_53") (pintype "output+no_connect"))
    )
    (net (code "87") (name "unconnected-(U15-~{OUT9}-Pad55)") (class "Default")
      (node (ref "U15") (pin "55") (pinfunction "~{OUT9}_55") (pintype "output+no_connect"))
    )
    (net (code "88") (name "unconnected-(XTAL1-VC-Pad1)") (class "Default")
      (node (ref "XTAL1") (pin "1") (pinfunction "VC_1") (pintype "passive+no_connect"))
    )
  )
)
